# POWER.net
KiCad netlist of a schematic drawn in Altium Designer
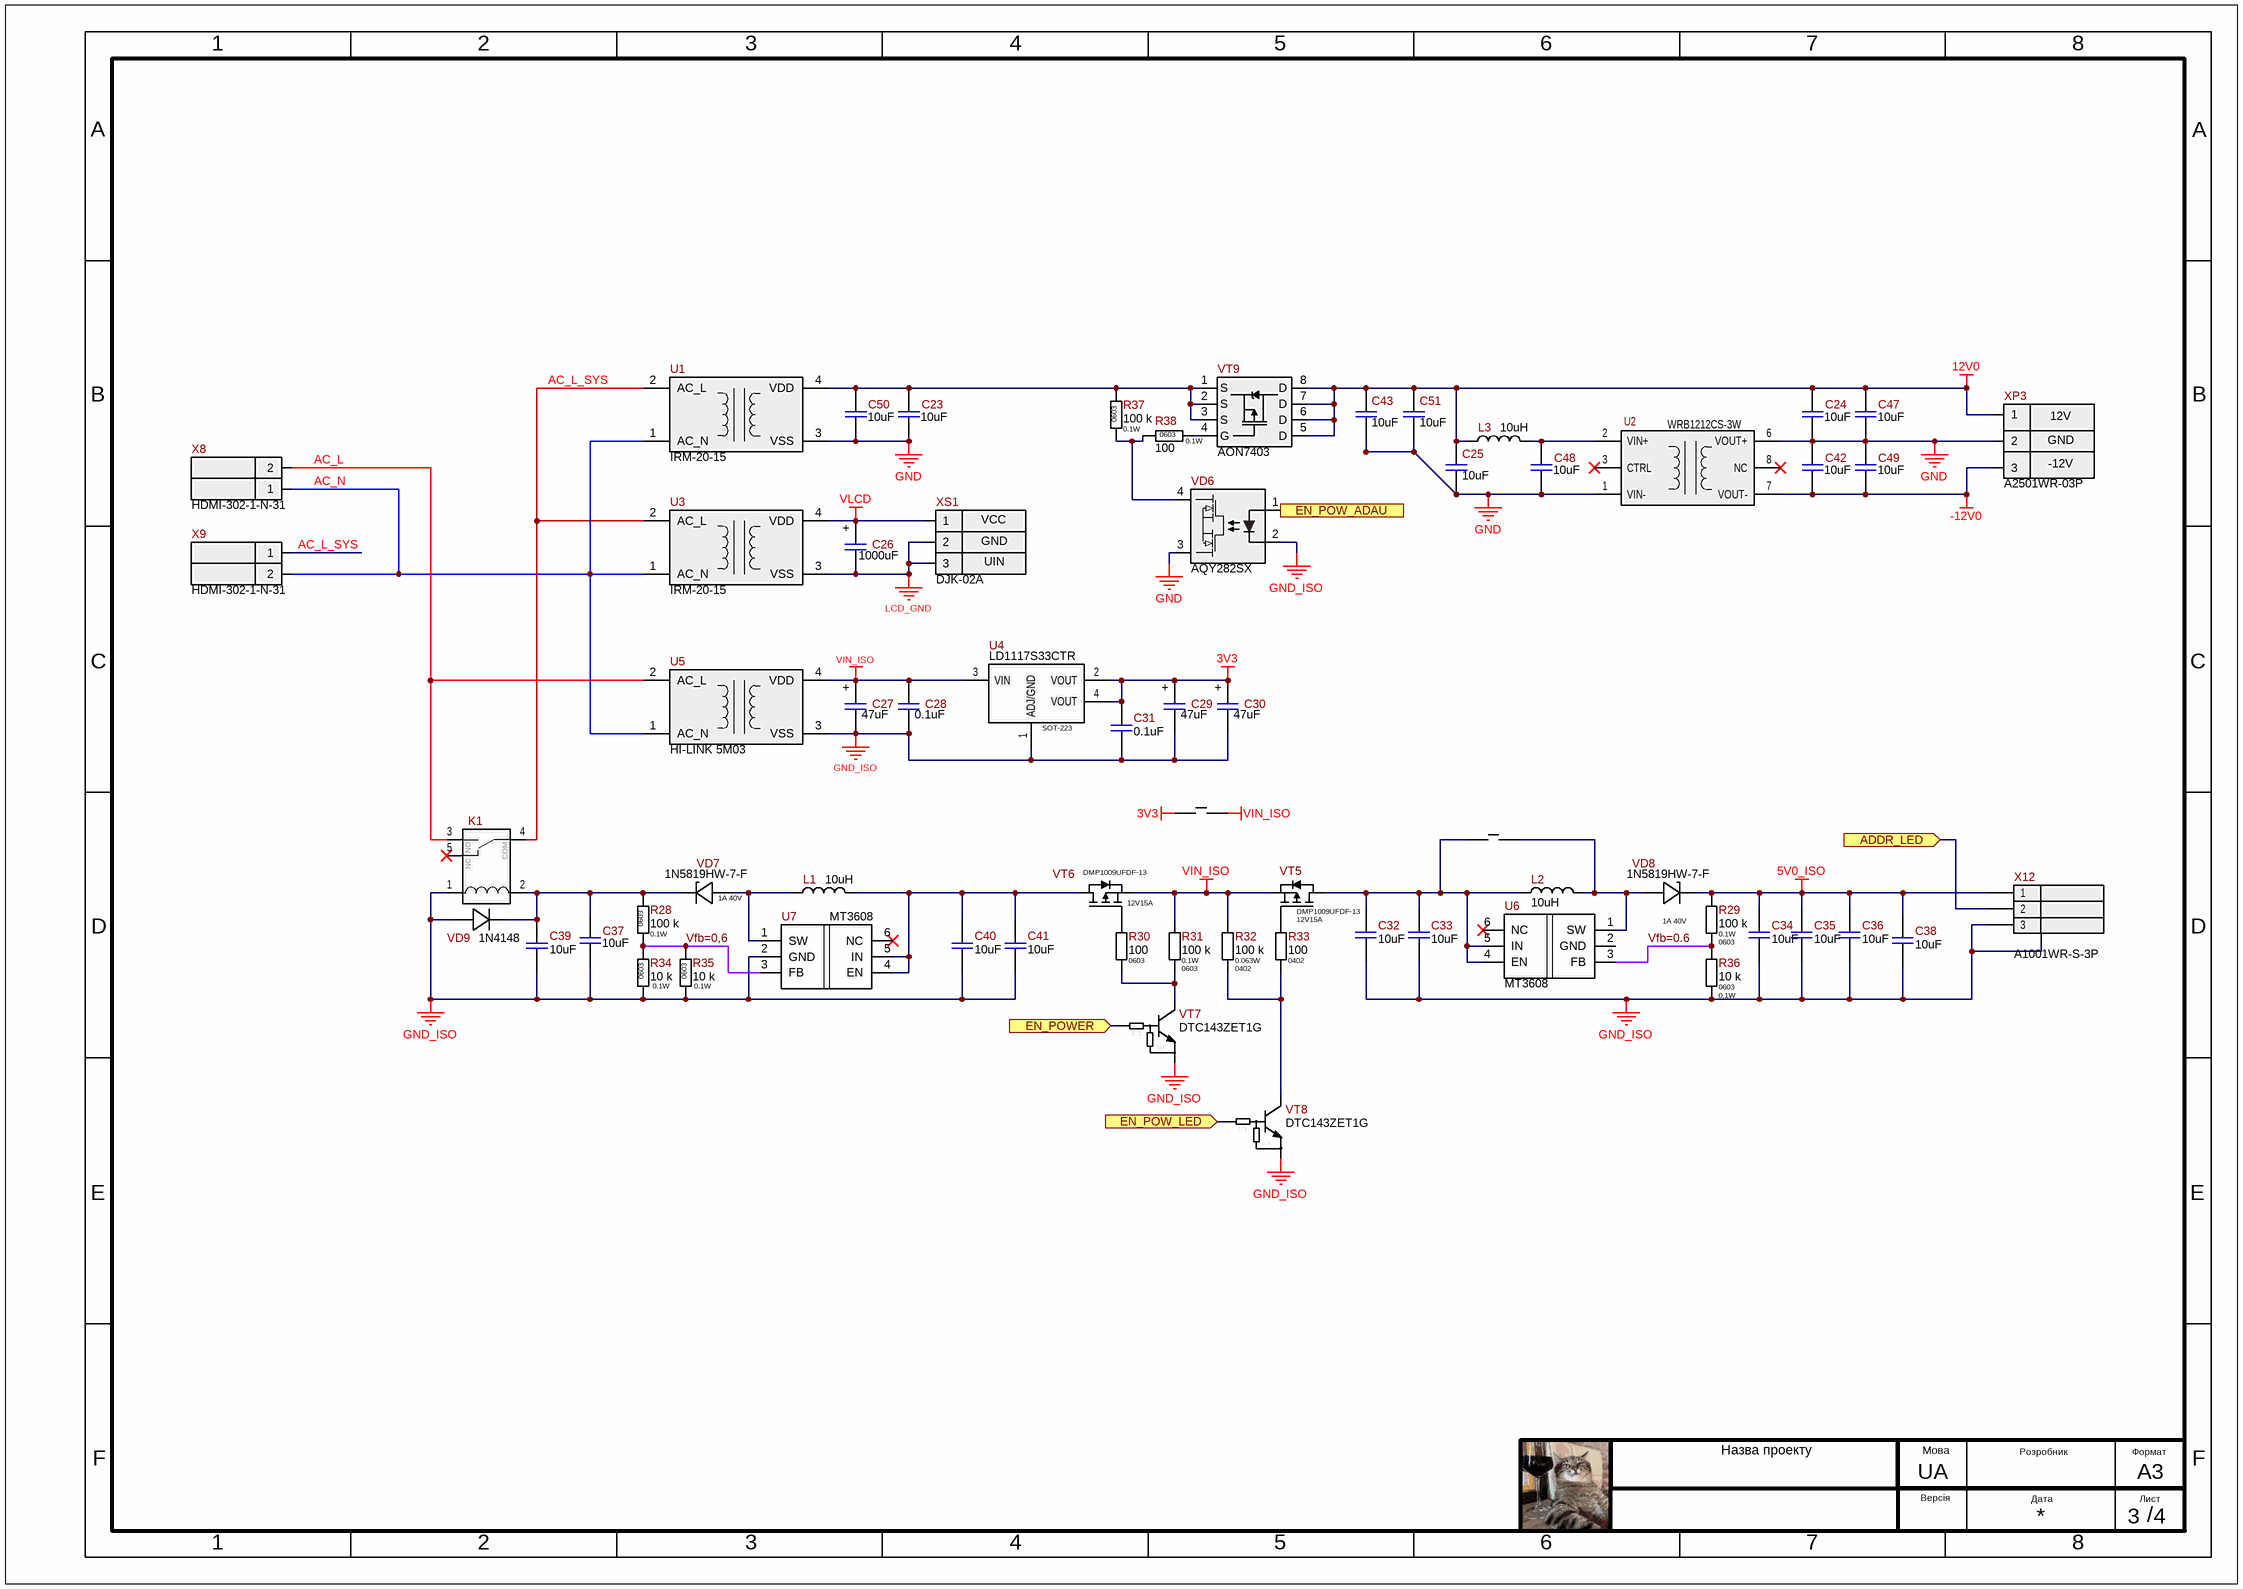
[diagram p0: POWER.SchDoc]

(export (version "E")
  (design (tool "Eeschema 10.0.6"))
  (components
    (comp (ref "C23")
      (value "10uF")
      (footprint "C0805(2012)")
      (description "CAP CER 10UF 16V X6S 0805")
      (fields (field (name "PART NUMBER") "10uF  16V C0805") (field (name "TOLERANCE") "±10%"))
      (libsource (lib "Database") (part "Capacitor_Ceramic"))
    )
    (comp (ref "C24")
      (value "10uF")
      (footprint "C0805(2012)")
      (description "CAP CER 10UF 16V X6S 0805")
      (fields (field (name "PART NUMBER") "10uF  16V C0805") (field (name "TOLERANCE") "±10%"))
      (libsource (lib "Database") (part "Capacitor_Ceramic"))
    )
    (comp (ref "C25")
      (value "10uF")
      (footprint "C0805(2012)")
      (description "CAP CER 10UF 16V X6S 0805")
      (fields (field (name "PART NUMBER") "10uF  16V C0805") (field (name "TOLERANCE") "±10%"))
      (libsource (lib "Database") (part "Capacitor_Ceramic"))
    )
    (comp (ref "C26")
      (value "1000uF")
      (footprint "CAP 10x16")
      (description "1000uF 20% 16V EHR 10x16mm")
      (fields (field (name "PART NUMBER") "1000uF  16V 10x16(EHR)") (field (name "TOLERANCE") "±20%"))
      (libsource (lib "Database") (part "Capacitor_Electrolytic"))
    )
    (comp (ref "C27")
      (value "47uF")
      (footprint "CASE_C(6032)")
      (description "CAP TANT 47UF 10% 20V 2312")
      (fields (field (name "PART NUMBER") "47uF  20V CASE-C") (field (name "TOLERANCE") "±10%"))
      (libsource (lib "Database") (part "Capacitor_Electrolytic"))
    )
    (comp (ref "C28")
      (value "0.1uF")
      (footprint "C0603(1608)")
      (description "CAP CER 0.1UF 50V X7R 0603")
      (fields (field (name "PART NUMBER") "0.1uF  50V C0603") (field (name "TOLERANCE") "±10%"))
      (libsource (lib "Database") (part "Capacitor_Ceramic"))
    )
    (comp (ref "C29")
      (value "47uF")
      (footprint "CASE_C(6032)")
      (description "CAP TANT 47UF 10% 20V 2312")
      (fields (field (name "PART NUMBER") "47uF  20V CASE-C") (field (name "TOLERANCE") "±10%"))
      (libsource (lib "Database") (part "Capacitor_Electrolytic"))
    )
    (comp (ref "C30")
      (value "47uF")
      (footprint "CASE_C(6032)")
      (description "CAP TANT 47UF 10% 20V 2312")
      (fields (field (name "PART NUMBER") "47uF  20V CASE-C") (field (name "TOLERANCE") "±10%"))
      (libsource (lib "Database") (part "Capacitor_Electrolytic"))
    )
    (comp (ref "C31")
      (value "0.1uF")
      (footprint "C0402(1005)")
      (description "CAP CER 0.1UF 25V X7R 0402")
      (fields (field (name "PART NUMBER") "0.1uF  25V C0402") (field (name "TOLERANCE") "±10%"))
      (libsource (lib "Database") (part "Capacitor_Ceramic"))
    )
    (comp (ref "C32")
      (value "10uF")
      (footprint "C0805(2012)")
      (description "CAP CER 10UF 16V X6S 0805")
      (fields (field (name "PART NUMBER") "10uF  16V C0805") (field (name "TOLERANCE") "±10%"))
      (libsource (lib "Database") (part "Capacitor_Ceramic"))
    )
    (comp (ref "C33")
      (value "10uF")
      (footprint "C0805(2012)")
      (description "CAP CER 10UF 16V X6S 0805")
      (fields (field (name "PART NUMBER") "10uF  16V C0805") (field (name "TOLERANCE") "±10%"))
      (libsource (lib "Database") (part "Capacitor_Ceramic"))
    )
    (comp (ref "C34")
      (value "10uF")
      (footprint "C0805(2012)")
      (description "CAP CER 10UF 16V X6S 0805")
      (fields (field (name "PART NUMBER") "10uF  16V C0805") (field (name "TOLERANCE") "±10%"))
      (libsource (lib "Database") (part "Capacitor_Ceramic"))
    )
    (comp (ref "C35")
      (value "10uF")
      (footprint "C0805(2012)")
      (description "CAP CER 10UF 16V X6S 0805")
      (fields (field (name "PART NUMBER") "10uF  16V C0805") (field (name "TOLERANCE") "±10%"))
      (libsource (lib "Database") (part "Capacitor_Ceramic"))
    )
    (comp (ref "C36")
      (value "10uF")
      (footprint "C0805(2012)")
      (description "CAP CER 10UF 16V X6S 0805")
      (fields (field (name "PART NUMBER") "10uF  16V C0805") (field (name "TOLERANCE") "±10%"))
      (libsource (lib "Database") (part "Capacitor_Ceramic"))
    )
    (comp (ref "C37")
      (value "10uF")
      (footprint "C0805(2012)")
      (description "CAP CER 10UF 16V X6S 0805")
      (fields (field (name "PART NUMBER") "10uF  16V C0805") (field (name "TOLERANCE") "±10%"))
      (libsource (lib "Database") (part "Capacitor_Ceramic"))
    )
    (comp (ref "C38")
      (value "10uF")
      (footprint "C0805(2012)")
      (description "CAP CER 10UF 16V X6S 0805")
      (fields (field (name "PART NUMBER") "10uF  16V C0805") (field (name "TOLERANCE") "±10%"))
      (libsource (lib "Database") (part "Capacitor_Ceramic"))
    )
    (comp (ref "C39")
      (value "10uF")
      (footprint "C0805(2012)")
      (description "CAP CER 10UF 16V X6S 0805")
      (fields (field (name "PART NUMBER") "10uF  16V C0805") (field (name "TOLERANCE") "±10%"))
      (libsource (lib "Database") (part "Capacitor_Ceramic"))
    )
    (comp (ref "C40")
      (value "10uF")
      (footprint "C0805(2012)")
      (description "CAP CER 10UF 16V X6S 0805")
      (fields (field (name "PART NUMBER") "10uF  16V C0805") (field (name "TOLERANCE") "±10%"))
      (libsource (lib "Database") (part "Capacitor_Ceramic"))
    )
    (comp (ref "C41")
      (value "10uF")
      (footprint "C0805(2012)")
      (description "CAP CER 10UF 16V X6S 0805")
      (fields (field (name "PART NUMBER") "10uF  16V C0805") (field (name "TOLERANCE") "±10%"))
      (libsource (lib "Database") (part "Capacitor_Ceramic"))
    )
    (comp (ref "C42")
      (value "10uF")
      (footprint "C0805(2012)")
      (description "CAP CER 10UF 16V X6S 0805")
      (fields (field (name "PART NUMBER") "10uF  16V C0805") (field (name "TOLERANCE") "±10%"))
      (libsource (lib "Database") (part "Capacitor_Ceramic"))
    )
    (comp (ref "C43")
      (value "10uF")
      (footprint "C0805(2012)")
      (description "CAP CER 10UF 16V X6S 0805")
      (fields (field (name "PART NUMBER") "10uF  16V C0805") (field (name "TOLERANCE") "±10%"))
      (libsource (lib "Database") (part "Capacitor_Ceramic"))
    )
    (comp (ref "C47")
      (value "10uF")
      (footprint "C0805(2012)")
      (description "CAP CER 10UF 16V X6S 0805")
      (fields (field (name "PART NUMBER") "10uF  16V C0805") (field (name "TOLERANCE") "±10%"))
      (libsource (lib "Database") (part "Capacitor_Ceramic"))
    )
    (comp (ref "C48")
      (value "10uF")
      (footprint "C0805(2012)")
      (description "CAP CER 10UF 16V X6S 0805")
      (fields (field (name "PART NUMBER") "10uF  16V C0805") (field (name "TOLERANCE") "±10%"))
      (libsource (lib "Database") (part "Capacitor_Ceramic"))
    )
    (comp (ref "C49")
      (value "10uF")
      (footprint "C0805(2012)")
      (description "CAP CER 10UF 16V X6S 0805")
      (fields (field (name "PART NUMBER") "10uF  16V C0805") (field (name "TOLERANCE") "±10%"))
      (libsource (lib "Database") (part "Capacitor_Ceramic"))
    )
    (comp (ref "C50")
      (value "10uF")
      (footprint "C0805(2012)")
      (description "CAP CER 10UF 16V X6S 0805")
      (fields (field (name "PART NUMBER") "10uF  16V C0805") (field (name "TOLERANCE") "±10%"))
      (libsource (lib "Database") (part "Capacitor_Ceramic"))
    )
    (comp (ref "C51")
      (value "10uF")
      (footprint "C0805(2012)")
      (description "CAP CER 10UF 16V X6S 0805")
      (fields (field (name "PART NUMBER") "10uF  16V C0805") (field (name "TOLERANCE") "±10%"))
      (libsource (lib "Database") (part "Capacitor_Ceramic"))
    )
    (comp (ref "K1")
      (value "LEG-12")
      (footprint "Relay10A")
      (description "General Purpose Relay, 1 Form C (1PDT), 12VDC 400Ohm Coil, 120VAC/24VDC @ 10A, 240VAC Max")
      (libsource (lib "Database") (part "RELAY10A"))
    )
    (comp (ref "L1")
      (value "10uH")
      (footprint "WE-LQS SMD 4018")
      (description "FIXED IND 10UH 1A 66 MOHM SMD")
      (fields (field (name "PART NUMBER") "NRS4018T3R3") (field (name "TOLERANCE") "±20"))
      (libsource (lib "Database") (part "INDUCTORS"))
    )
    (comp (ref "L2")
      (value "10uH")
      (footprint "WE-LQS SMD 4018")
      (description "FIXED IND 10UH 1A 66 MOHM SMD")
      (fields (field (name "PART NUMBER") "NRS4018T3R3") (field (name "TOLERANCE") "±20"))
      (libsource (lib "") (part "INDUCTORS_1"))
    )
    (comp (ref "L3")
      (value "10uH")
      (footprint "WE-LQS SMD 4018")
      (description "FIXED IND 10UH 1A 66 MOHM SMD")
      (fields (field (name "PART NUMBER") "NRS4018T3R3") (field (name "TOLERANCE") "±20"))
      (libsource (lib "Database") (part "INDUCTORS"))
    )
    (comp (ref "R28")
      (value "100 k")
      (footprint "R0603")
      (description "RES SMD 100 k OHM  ±1% 1/10W 0603")
      (fields
        (field (name "POWER RATING") "0.1W")
        (field (name "PACKAGE/CASE") "0603")
        (field (name "PART NUMBER") "100 k  R0603")
        (field (name "TOLERANCE") "±1%")
      )
      (libsource (lib "Database") (part "R0603"))
    )
    (comp (ref "R29")
      (value "100 k")
      (footprint "R0603")
      (description "RES SMD 100 k OHM  ±1% 1/10W 0603")
      (fields
        (field (name "POWER RATING") "0.1W")
        (field (name "PACKAGE/CASE") "0603")
        (field (name "PART NUMBER") "100 k  R0603")
        (field (name "TOLERANCE") "±1%")
      )
      (libsource (lib "Database") (part "R0603"))
    )
    (comp (ref "R30")
      (value "100")
      (footprint "R0603")
      (description "RES SMD 100 OHM  ±1% 1/10W 0603")
      (fields
        (field (name "PACKAGE/CASE") "0603")
        (field (name "PART NUMBER") "100  R0603")
        (field (name "TOLERANCE") "±1%")
      )
      (libsource (lib "Database") (part "R0603"))
    )
    (comp (ref "R31")
      (value "100 k")
      (footprint "R0603")
      (description "RES SMD 100 k OHM  ±1% 1/10W 0603")
      (fields
        (field (name "POWER RATING") "0.1W")
        (field (name "PACKAGE/CASE") "0603")
        (field (name "PART NUMBER") "100 k  R0603")
        (field (name "TOLERANCE") "±1%")
      )
      (libsource (lib "Database") (part "R0603"))
    )
    (comp (ref "R32")
      (value "100 k")
      (footprint "R0402")
      (description "RES SMD 100 k OHM  ±1% 1/16W 0402")
      (fields
        (field (name "POWER RATING") "0.063W")
        (field (name "PACKAGE/CASE") "0402")
        (field (name "PART NUMBER") "100 k  R0402")
        (field (name "TOLERANCE") "±1%")
      )
      (libsource (lib "Database") (part "R0402"))
    )
    (comp (ref "R33")
      (value "100")
      (footprint "R0402")
      (description "RES SMD 100 OHM  ±1% 1/16W 0402")
      (fields
        (field (name "PACKAGE/CASE") "0402")
        (field (name "PART NUMBER") "100  R0402")
        (field (name "TOLERANCE") "±1%")
      )
      (libsource (lib "Database") (part "R0402"))
    )
    (comp (ref "R34")
      (value "10 k")
      (footprint "R0603")
      (description "RES SMD 10 k OHM  ±1% 1/10W 0603")
      (fields
        (field (name "PACKAGE/CASE") "0603")
        (field (name "POWER RATING") "0.1W")
        (field (name "PART NUMBER") "10 k  R0603")
        (field (name "TOLERANCE") "±1%")
      )
      (libsource (lib "Database") (part "R0603"))
    )
    (comp (ref "R35")
      (value "10 k")
      (footprint "R0603")
      (description "RES SMD 10 k OHM  ±1% 1/10W 0603")
      (fields
        (field (name "PACKAGE/CASE") "0603")
        (field (name "POWER RATING") "0.1W")
        (field (name "PART NUMBER") "10 k  R0603")
        (field (name "TOLERANCE") "±1%")
      )
      (libsource (lib "Database") (part "R0603"))
    )
    (comp (ref "R36")
      (value "10 k")
      (footprint "R0603")
      (description "RES SMD 10 k OHM  ±1% 1/10W 0603")
      (fields
        (field (name "PACKAGE/CASE") "0603")
        (field (name "POWER RATING") "0.1W")
        (field (name "PART NUMBER") "10 k  R0603")
        (field (name "TOLERANCE") "±1%")
      )
      (libsource (lib "Database") (part "R0603"))
    )
    (comp (ref "R37")
      (value "100 k")
      (footprint "R0603")
      (description "RES SMD 100 k OHM  ±1% 1/10W 0603")
      (fields
        (field (name "POWER RATING") "0.1W")
        (field (name "PACKAGE/CASE") "0603")
        (field (name "PART NUMBER") "100 k  R0603")
        (field (name "TOLERANCE") "±1%")
      )
      (libsource (lib "Database") (part "R0603"))
    )
    (comp (ref "R38")
      (value "100")
      (footprint "R0603")
      (description "RES SMD 100 OHM  ±1% 1/10W 0603")
      (fields
        (field (name "POWER RATING") "0.1W")
        (field (name "PACKAGE/CASE") "0603")
        (field (name "PART NUMBER") "100  R0603")
        (field (name "TOLERANCE") "±1%")
      )
      (libsource (lib "Database") (part "R0603"))
    )
    (comp (ref "U1")
      (value "IRM-20-15")
      (footprint "IRM-20-xx_REC")
      (description "15W 85-264V AC-DC PCB-Mount Green Power Module, 15V @ 1.4A")
      (libsource (lib "Database") (part "HI-LINK XXMXX"))
    )
    (comp (ref "U2")
      (value "WRB1212CS-3W")
      (footprint "SIP-8 22.0x9.5x12.0mm 6pin")
      (description "3W DC/DC Power Supply, Vout 12V, Size 22.0x9.5x12.0mm")
      (fields (field (name "MANUFACTURER") "rlt") (field (name "PART NUMBER") "{Part Number}"))
      (libsource (lib "Database") (part "WRB1212CS-3W"))
    )
    (comp (ref "U3")
      (value "IRM-20-15")
      (footprint "IRM-20-xx_REC")
      (description "15W 85-264V AC-DC PCB-Mount Green Power Module, 15V @ 1.4A")
      (libsource (lib "Database") (part "HI-LINK XXMXX"))
    )
    (comp (ref "U4")
      (value "LD1117STR")
      (footprint "SOT223")
      (description "IC REG LINEAR 3.3V 800MA SOT223")
      (fields
        (field (name "MANUFACTURER") "STMicroelectronics")
        (field (name "PACKAGE") "SOT-223")
        (field (name "PART NUMBER") "LD1117S33CTR")
      )
      (libsource (lib "Database") (part "LD1117S"))
    )
    (comp (ref "U5")
      (value "HI-LINK 5M03")
      (footprint "HLINK_5MXX")
      (description "85-264VAC  5W 3.3V 1.5A")
      (libsource (lib "Database") (part "HI-LINK XXMXX"))
    )
    (comp (ref "U6")
      (value "MT3608")
      (footprint "SOT23-6")
      (description "HIGH EFFICIENCY 1.2MHZ 2A STEP UP CONVERTER")
      (fields (field (name "MANUFACTURER") "AEROSEMI"))
      (libsource (lib "Database") (part "MT3608"))
    )
    (comp (ref "U7")
      (value "MT3608")
      (footprint "SOT23-6")
      (description "HIGH EFFICIENCY 1.2MHZ 2A STEP UP CONVERTER")
      (fields (field (name "MANUFACTURER") "AEROSEMI"))
      (libsource (lib "") (part "MT3608_1"))
    )
    (comp (ref "VD6")
      (value "AQY282SX")
      (footprint "SOP-4N")
      (description "SSR RELAY SPST-NO 500MA 0-60V")
      (fields (field (name "MANUFACTURER") "Panasonic Electric Works"))
      (libsource (lib "Database") (part "AQY282SX"))
    )
    (comp (ref "VD7")
      (value "1N5819HW-7-F")
      (footprint "SOD-123")
      (description "DIODE SCHOTTKY 40V 1A SOD-123")
      (fields (field (name "POWER RATING") "1A 40V") (field (name "MANUFACTURER") "Diodes Incorporated"))
      (libsource (lib "Database") (part "SCHOTTKY"))
    )
    (comp (ref "VD8")
      (value "1N5819HW-7-F")
      (footprint "SOD-123")
      (description "DIODE SCHOTTKY 40V 1A SOD-123")
      (fields (field (name "POWER RATING") "1A 40V") (field (name "MANUFACTURER") "Diodes Incorporated"))
      (libsource (lib "Database") (part "SCHOTTKY"))
    )
    (comp (ref "VD9")
      (value "1N4148")
      (footprint "SOD-80")
      (description "DIODE GEN PURP 75V 250MA SOD323")
      (fields (field (name "MANUFACTURER") "Diodes Incorporated"))
      (libsource (lib "Database") (part "DIODE"))
    )
    (comp (ref "VT5")
      (value "DMP1009UFDF-13")
      (footprint "U-DFN2020-6_SLDR")
      (description "P-Channel 12 V 15A (Ta) 2W (Ta) Surface Mount U-DFN2020-6 (Type F)")
      (fields (field (name "POWER RATING") "12V15A") (field (name "MANUFACTURER") "Diodes Incorporated"))
      (libsource (lib "Database") (part "DMP1009UFDF"))
    )
    (comp (ref "VT6")
      (value "DMP1009UFDF-13")
      (footprint "U-DFN2020-6_SLDR")
      (description "P-Channel 12 V 15A (Ta) 2W (Ta) Surface Mount U-DFN2020-6 (Type F)")
      (fields (field (name "POWER RATING") "12V15A") (field (name "MANUFACTURER") "Diodes Incorporated"))
      (libsource (lib "Database") (part "DMP1009UFDF"))
    )
    (comp (ref "VT7")
      (value "DTC143ZET1G")
      (footprint "SOT-416")
      (description "TRANS PREBIAS NPN 50V 100MA SC75")
      (fields (field (name "MANUFACTURER") "onsemi"))
      (libsource (lib "Database") (part "Bipolar_NPN_Pre-Biased"))
    )
    (comp (ref "VT8")
      (value "DTC143ZET1G")
      (footprint "SOT-416")
      (description "TRANS PREBIAS NPN 50V 100MA SC75")
      (fields (field (name "MANUFACTURER") "onsemi"))
      (libsource (lib "Database") (part "Bipolar_NPN_Pre-Biased"))
    )
    (comp (ref "VT9")
      (value "AON7403")
      (footprint "DFN3X3")
      (description "P-Channel 30 V 11A (Ta), 29A (Tc) 3.1W (Ta), 25W (Tc) Surface Mount 8-DFN-EP (3x3)")
      (fields
        (field (name "PART NUMBER") "AON7403")
        (field (name "MANUFACTURER") "Alpha & Omega Semiconductor Inc.")
      )
      (libsource (lib "Database") (part "AON7403"))
    )
    (comp (ref "X8")
      (value "DG300-7.5-02P-13-02Z(H)")
      (footprint "DG300-7.5-02P-13-02Z(H)")
      (description "Screw Terminal, 7.5mm Pitch, 2 pin, Black")
      (fields (field (name "PART NUMBER") "HDMI-302-1-N-31") (field (name "MANUFACTURER") "Degson"))
      (libsource (lib "Database") (part "CON_2"))
    )
    (comp (ref "X9")
      (value "DG300-7.5-02P-13-02Z(H)")
      (footprint "DG300-7.5-02P-13-02Z(H)")
      (description "Screw Terminal, 7.5mm Pitch, 2 pin, Black")
      (fields (field (name "PART NUMBER") "HDMI-302-1-N-31") (field (name "MANUFACTURER") "Degson"))
      (libsource (lib "") (part "CON_2_1"))
    )
    (comp (ref "X10")
      (value "Jumper 1.5х2")
      (footprint "NetTie1.5х2")
      (description "Jumper 1.5mm x 2mm")
      (libsource (lib "Database") (part "NetTie"))
    )
    (comp (ref "X11")
      (value "Jumper 1.5х2")
      (footprint "NetTie1.5х2")
      (description "Jumper 1.5mm x 2mm")
      (libsource (lib "Database") (part "NetTie"))
    )
    (comp (ref "X12")
      (value "A1001WR-S-3P")
      (footprint "A1001WR-S-03P")
      (description "CONN HEADER 3POS 1MM")
      (fields (field (name "MANUFACTURER") "Joint Tech"))
      (libsource (lib "Database") (part "A1001WR-S-03P"))
    )
    (comp (ref "XP3")
      (value "A2501WR-03P")
      (footprint "A2501WR-03P")
      (description "PIN: 3; A2501; 3A; 250V; UL94V-0")
      (fields (field (name "MANUFACTURER") "JOINT TECH"))
      (libsource (lib "Database") (part "CON_3"))
    )
    (comp (ref "XS1")
      (value "DJK-02A")
      (footprint "DC-140-003")
      (description "DC POWER JACK CONNECTOR 6.3MM")
      (fields (field (name "MANUFACTURER") "KLS"))
      (libsource (lib "Database") (part "DJK-02A"))
    )
  )
  (nets
    (net (code "1") (name "-12V0") (class "Default")
      (node (ref "C42") (pin "2") (pinfunction "2_2") (pintype "passive"))
      (node (ref "C49") (pin "2") (pinfunction "2_2") (pintype "passive"))
      (node (ref "U2") (pin "7") (pinfunction "VOUT-_7") (pintype "passive"))
      (node (ref "XP3") (pin "3") (pinfunction "3_3") (pintype "passive"))
    )
    (net (code "2") (name "/AC_L") (class "Default")
      (node (ref "K1") (pin "3") (pinfunction "NO_3") (pintype "passive"))
      (node (ref "U5") (pin "2") (pinfunction "AC_L_2") (pintype "passive"))
      (node (ref "X8") (pin "2") (pinfunction "2_2") (pintype "passive"))
    )
    (net (code "3") (name "/AC_L_SYS") (class "Default")
      (node (ref "K1") (pin "4") (pinfunction "COM_4") (pintype "passive"))
      (node (ref "U1") (pin "2") (pinfunction "AC_L_2") (pintype "passive"))
      (node (ref "U3") (pin "2") (pinfunction "AC_L_2") (pintype "passive"))
      (node (ref "X9") (pin "1") (pinfunction "1_1") (pintype "passive"))
    )
    (net (code "4") (name "/AC_N") (class "Default")
      (node (ref "U1") (pin "1") (pinfunction "AC_N_1") (pintype "passive"))
      (node (ref "U3") (pin "1") (pinfunction "AC_N_1") (pintype "passive"))
      (node (ref "U5") (pin "1") (pinfunction "AC_N_1") (pintype "passive"))
      (node (ref "X8") (pin "1") (pinfunction "1_1") (pintype "passive"))
      (node (ref "X9") (pin "2") (pinfunction "2_2") (pintype "passive"))
    )
    (net (code "5") (name "/ADDR_LED") (class "Default")
      (node (ref "X12") (pin "2") (pinfunction "2_2") (pintype "passive"))
    )
    (net (code "6") (name "/EN_POWER") (class "Default")
      (node (ref "VT7") (pin "1") (pinfunction "B_1") (pintype "passive"))
    )
    (net (code "7") (name "/EN_POW_ADAU") (class "Default")
      (node (ref "VD6") (pin "1") (pinfunction "VIN_1") (pintype "passive"))
    )
    (net (code "8") (name "/EN_POW_LED") (class "Default")
      (node (ref "VT8") (pin "1") (pinfunction "B_1") (pintype "passive"))
    )
    (net (code "9") (name "/Vfb=0,6") (class "Default")
      (node (ref "R28") (pin "1") (pinfunction "1_1") (pintype "passive"))
      (node (ref "R34") (pin "2") (pinfunction "2_2") (pintype "passive"))
      (node (ref "R35") (pin "2") (pinfunction "2_2") (pintype "passive"))
      (node (ref "U7") (pin "3") (pinfunction "FB_3") (pintype "passive"))
    )
    (net (code "10") (name "/Vfb=0.6") (class "Default")
      (node (ref "R29") (pin "1") (pinfunction "1_1") (pintype "passive"))
      (node (ref "R36") (pin "2") (pinfunction "2_2") (pintype "passive"))
      (node (ref "U6") (pin "3") (pinfunction "FB_3") (pintype "passive"))
    )
    (net (code "11") (name "3V3") (class "Default")
      (node (ref "C29") (pin "1") (pinfunction "1_1") (pintype "passive"))
      (node (ref "C30") (pin "1") (pinfunction "1_1") (pintype "passive"))
      (node (ref "C31") (pin "1") (pinfunction "1_1") (pintype "passive"))
      (node (ref "U4") (pin "2") (pinfunction "VOUT_2") (pintype "passive"))
      (node (ref "U4") (pin "4") (pinfunction "VOUT_4") (pintype "passive"))
      (node (ref "X10") (pin "1") (pinfunction "1_1") (pintype "passive"))
    )
    (net (code "12") (name "5V0_ISO") (class "Default")
      (node (ref "C34") (pin "1") (pinfunction "1_1") (pintype "passive"))
      (node (ref "C35") (pin "1") (pinfunction "1_1") (pintype "passive"))
      (node (ref "C36") (pin "1") (pinfunction "1_1") (pintype "passive"))
      (node (ref "C38") (pin "1") (pinfunction "1_1") (pintype "passive"))
      (node (ref "R29") (pin "2") (pinfunction "2_2") (pintype "passive"))
      (node (ref "VD8") (pin "1") (pinfunction "K_1") (pintype "passive"))
      (node (ref "X12") (pin "1") (pinfunction "1_1") (pintype "passive"))
    )
    (net (code "13") (name "12V0") (class "Default")
      (node (ref "C24") (pin "1") (pinfunction "1_1") (pintype "passive"))
      (node (ref "C25") (pin "1") (pinfunction "1_1") (pintype "passive"))
      (node (ref "C43") (pin "1") (pinfunction "1_1") (pintype "passive"))
      (node (ref "C47") (pin "1") (pinfunction "1_1") (pintype "passive"))
      (node (ref "C51") (pin "1") (pinfunction "1_1") (pintype "passive"))
      (node (ref "L3") (pin "2") (pintype "passive"))
      (node (ref "VT9") (pin "5") (pinfunction "D_5") (pintype "passive"))
      (node (ref "VT9") (pin "6") (pinfunction "D_6") (pintype "passive"))
      (node (ref "VT9") (pin "7") (pinfunction "D_7") (pintype "passive"))
      (node (ref "VT9") (pin "8") (pinfunction "D_8") (pintype "passive"))
      (node (ref "XP3") (pin "1") (pinfunction "1_1") (pintype "passive"))
    )
    (net (code "14") (name "GND") (class "Default")
      (node (ref "C23") (pin "2") (pinfunction "2_2") (pintype "passive"))
      (node (ref "C24") (pin "2") (pinfunction "2_2") (pintype "passive"))
      (node (ref "C25") (pin "2") (pinfunction "2_2") (pintype "passive"))
      (node (ref "C42") (pin "1") (pinfunction "1_1") (pintype "passive"))
      (node (ref "C43") (pin "2") (pinfunction "2_2") (pintype "passive"))
      (node (ref "C47") (pin "2") (pinfunction "2_2") (pintype "passive"))
      (node (ref "C48") (pin "2") (pinfunction "2_2") (pintype "passive"))
      (node (ref "C49") (pin "1") (pinfunction "1_1") (pintype "passive"))
      (node (ref "C50") (pin "2") (pinfunction "2_2") (pintype "passive"))
      (node (ref "C51") (pin "2") (pinfunction "2_2") (pintype "passive"))
      (node (ref "U1") (pin "3") (pinfunction "VSS_3") (pintype "passive"))
      (node (ref "U2") (pin "1") (pinfunction "VIN-_1") (pintype "passive"))
      (node (ref "U2") (pin "6") (pinfunction "VOUT+_6") (pintype "passive"))
      (node (ref "VD6") (pin "3") (pinfunction "3_3") (pintype "passive"))
      (node (ref "XP3") (pin "2") (pinfunction "2_2") (pintype "passive"))
    )
    (net (code "15") (name "GND_ISO") (class "Default")
      (node (ref "C27") (pin "2") (pinfunction "2_2") (pintype "passive"))
      (node (ref "C28") (pin "2") (pinfunction "2_2") (pintype "passive"))
      (node (ref "C29") (pin "2") (pinfunction "2_2") (pintype "passive"))
      (node (ref "C30") (pin "2") (pinfunction "2_2") (pintype "passive"))
      (node (ref "C31") (pin "2") (pinfunction "2_2") (pintype "passive"))
      (node (ref "C32") (pin "2") (pinfunction "2_2") (pintype "passive"))
      (node (ref "C33") (pin "2") (pinfunction "2_2") (pintype "passive"))
      (node (ref "C34") (pin "2") (pinfunction "2_2") (pintype "passive"))
      (node (ref "C35") (pin "2") (pinfunction "2_2") (pintype "passive"))
      (node (ref "C36") (pin "2") (pinfunction "2_2") (pintype "passive"))
      (node (ref "C37") (pin "2") (pinfunction "2_2") (pintype "passive"))
      (node (ref "C38") (pin "2") (pinfunction "2_2") (pintype "passive"))
      (node (ref "C39") (pin "2") (pinfunction "2_2") (pintype "passive"))
      (node (ref "C40") (pin "2") (pinfunction "2_2") (pintype "passive"))
      (node (ref "C41") (pin "2") (pinfunction "2_2") (pintype "passive"))
      (node (ref "K1") (pin "1") (pintype "passive"))
      (node (ref "R34") (pin "1") (pinfunction "1_1") (pintype "passive"))
      (node (ref "R35") (pin "1") (pinfunction "1_1") (pintype "passive"))
      (node (ref "R36") (pin "1") (pinfunction "1_1") (pintype "passive"))
      (node (ref "U4") (pin "1") (pinfunction "ADJ/GND_1") (pintype "passive"))
      (node (ref "U5") (pin "3") (pinfunction "VSS_3") (pintype "passive"))
      (node (ref "U7") (pin "2") (pinfunction "GND_2") (pintype "power_in"))
      (node (ref "VD6") (pin "2") (pinfunction "GND_2") (pintype "passive"))
      (node (ref "VD9") (pin "2") (pinfunction "A_2") (pintype "passive"))
      (node (ref "VT7") (pin "2") (pinfunction "E_2") (pintype "passive"))
      (node (ref "VT8") (pin "2") (pinfunction "E_2") (pintype "passive"))
      (node (ref "X12") (pin "3") (pinfunction "3_3") (pintype "passive"))
      (node (ref "X12") (pin "MP") (pinfunction "MountPad_MP") (pintype "passive"))
    )
    (net (code "16") (name "LCD_GND") (class "Default")
      (node (ref "C26") (pin "2") (pinfunction "2_2") (pintype "passive"))
      (node (ref "U3") (pin "3") (pinfunction "VSS_3") (pintype "passive"))
      (node (ref "XS1") (pin "2") (pinfunction "2_2") (pintype "passive"))
      (node (ref "XS1") (pin "3") (pinfunction "3_3") (pintype "passive"))
    )
    (net (code "17") (name "Net-(R30-Pad2)") (class "Default")
      (node (ref "R30") (pin "2") (pinfunction "2_2") (pintype "passive"))
      (node (ref "VT6") (pin "G") (pinfunction "G_G") (pintype "passive"))
    )
    (net (code "18") (name "Net-(R33-Pad2)") (class "Default")
      (node (ref "R33") (pin "2") (pinfunction "2_2") (pintype "passive"))
      (node (ref "VT5") (pin "G") (pinfunction "G_G") (pintype "passive"))
    )
    (net (code "19") (name "Net-(R37-Pad1)") (class "Default")
      (node (ref "R37") (pin "1") (pinfunction "1_1") (pintype "passive"))
      (node (ref "R38") (pin "2") (pinfunction "2_2") (pintype "passive"))
      (node (ref "VD6") (pin "4") (pinfunction "4_4") (pintype "passive"))
    )
    (net (code "20") (name "Net-(U1-VDD)") (class "Default")
      (node (ref "C23") (pin "1") (pinfunction "1_1") (pintype "passive"))
      (node (ref "C50") (pin "1") (pinfunction "1_1") (pintype "passive"))
      (node (ref "R37") (pin "2") (pinfunction "2_2") (pintype "passive"))
      (node (ref "U1") (pin "4") (pinfunction "VDD_4") (pintype "passive"))
      (node (ref "VT9") (pin "1") (pinfunction "S_1") (pintype "passive"))
      (node (ref "VT9") (pin "2") (pinfunction "S_2") (pintype "passive"))
      (node (ref "VT9") (pin "3") (pinfunction "S_3") (pintype "passive"))
    )
    (net (code "21") (name "Net-(U2-VIN+)") (class "Default")
      (node (ref "C48") (pin "1") (pinfunction "1_1") (pintype "passive"))
      (node (ref "L3") (pin "1") (pintype "passive"))
      (node (ref "U2") (pin "2") (pinfunction "VIN+_2") (pintype "passive"))
    )
    (net (code "22") (name "Net-(U6-EN)") (class "Default")
      (node (ref "C32") (pin "1") (pinfunction "1_1") (pintype "passive"))
      (node (ref "C33") (pin "1") (pinfunction "1_1") (pintype "passive"))
      (node (ref "L2") (pin "1") (pintype "passive"))
      (node (ref "U6") (pin "4") (pinfunction "EN_4") (pintype "passive"))
      (node (ref "U6") (pin "5") (pinfunction "IN_5") (pintype "passive"))
      (node (ref "VT5") (pin "D") (pinfunction "D_D") (pintype "passive"))
      (node (ref "X11") (pin "2") (pinfunction "2_2") (pintype "passive"))
    )
    (net (code "23") (name "Net-(U6-SW)") (class "Default")
      (node (ref "L2") (pin "2") (pintype "passive"))
      (node (ref "U6") (pin "1") (pinfunction "SW_1") (pintype "power_in"))
      (node (ref "VD8") (pin "2") (pinfunction "A_2") (pintype "passive"))
      (node (ref "X11") (pin "1") (pinfunction "1_1") (pintype "passive"))
    )
    (net (code "24") (name "Net-(U7-EN)") (class "Default")
      (node (ref "C40") (pin "1") (pinfunction "1_1") (pintype "passive"))
      (node (ref "C41") (pin "1") (pinfunction "1_1") (pintype "passive"))
      (node (ref "L1") (pin "1") (pintype "passive"))
      (node (ref "U7") (pin "4") (pinfunction "EN_4") (pintype "passive"))
      (node (ref "U7") (pin "5") (pinfunction "IN_5") (pintype "passive"))
      (node (ref "VT6") (pin "D") (pinfunction "D_D") (pintype "passive"))
    )
    (net (code "25") (name "Net-(U7-SW)") (class "Default")
      (node (ref "L1") (pin "2") (pintype "passive"))
      (node (ref "U7") (pin "1") (pinfunction "SW_1") (pintype "power_in"))
      (node (ref "VD7") (pin "2") (pinfunction "A_2") (pintype "passive"))
    )
    (net (code "26") (name "Net-(VD7-K)") (class "Default")
      (node (ref "C37") (pin "1") (pinfunction "1_1") (pintype "passive"))
      (node (ref "C39") (pin "1") (pinfunction "1_1") (pintype "passive"))
      (node (ref "K1") (pin "2") (pintype "passive"))
      (node (ref "R28") (pin "2") (pinfunction "2_2") (pintype "passive"))
      (node (ref "VD7") (pin "1") (pinfunction "K_1") (pintype "passive"))
      (node (ref "VD9") (pin "1") (pinfunction "K_1") (pintype "passive"))
    )
    (net (code "27") (name "Net-(VT7-C)") (class "Default")
      (node (ref "R30") (pin "1") (pinfunction "1_1") (pintype "passive"))
      (node (ref "R31") (pin "1") (pinfunction "1_1") (pintype "passive"))
      (node (ref "VT7") (pin "3") (pinfunction "C_3") (pintype "passive"))
    )
    (net (code "28") (name "Net-(VT8-C)") (class "Default")
      (node (ref "R32") (pin "1") (pinfunction "1_1") (pintype "passive"))
      (node (ref "R33") (pin "1") (pinfunction "1_1") (pintype "passive"))
      (node (ref "VT8") (pin "3") (pinfunction "C_3") (pintype "passive"))
    )
    (net (code "29") (name "Net-(VT9-G)") (class "Default")
      (node (ref "R38") (pin "1") (pinfunction "1_1") (pintype "passive"))
      (node (ref "VT9") (pin "4") (pinfunction "G_4") (pintype "passive"))
    )
    (net (code "30") (name "VIN_ISO") (class "Default")
      (node (ref "C27") (pin "1") (pinfunction "1_1") (pintype "passive"))
      (node (ref "C28") (pin "1") (pinfunction "1_1") (pintype "passive"))
      (node (ref "R31") (pin "2") (pinfunction "2_2") (pintype "passive"))
      (node (ref "R32") (pin "2") (pinfunction "2_2") (pintype "passive"))
      (node (ref "U4") (pin "3") (pinfunction "VIN_3") (pintype "passive"))
      (node (ref "U5") (pin "4") (pinfunction "VDD_4") (pintype "passive"))
      (node (ref "VT5") (pin "S") (pinfunction "S_S") (pintype "passive"))
      (node (ref "VT6") (pin "S") (pinfunction "S_S") (pintype "passive"))
      (node (ref "X10") (pin "2") (pinfunction "2_2") (pintype "passive"))
    )
    (net (code "31") (name "VLCD") (class "Default")
      (node (ref "C26") (pin "1") (pinfunction "1_1") (pintype "passive"))
      (node (ref "U3") (pin "4") (pinfunction "VDD_4") (pintype "passive"))
      (node (ref "XS1") (pin "1") (pinfunction "1_1") (pintype "passive"))
    )
    (net (code "32") (name "unconnected-(K1-NC-Pad5)") (class "Default")
      (node (ref "K1") (pin "5") (pinfunction "NC_5") (pintype "passive+no_connect"))
    )
    (net (code "33") (name "unconnected-(U2-CTRL-Pad3)") (class "Default")
      (node (ref "U2") (pin "3") (pinfunction "CTRL_3") (pintype "passive+no_connect"))
    )
    (net (code "34") (name "unconnected-(U2-NC-Pad8)") (class "Default")
      (node (ref "U2") (pin "8") (pinfunction "NC_8") (pintype "passive+no_connect"))
    )
    (net (code "35") (name "unconnected-(U6-GND-Pad2)") (class "Default")
      (node (ref "U6") (pin "2") (pinfunction "GND_2") (pintype "power_in"))
    )
    (net (code "36") (name "unconnected-(U6-NC-Pad6)") (class "Default")
      (node (ref "U6") (pin "6") (pinfunction "NC_6") (pintype "passive+no_connect"))
    )
    (net (code "37") (name "unconnected-(U7-NC-Pad6)") (class "Default")
      (node (ref "U7") (pin "6") (pinfunction "NC_6") (pintype "passive+no_connect"))
    )
  )
)
